# 5V_SYS_SUPPLY.net
KiCad netlist of a schematic drawn in Altium Designer
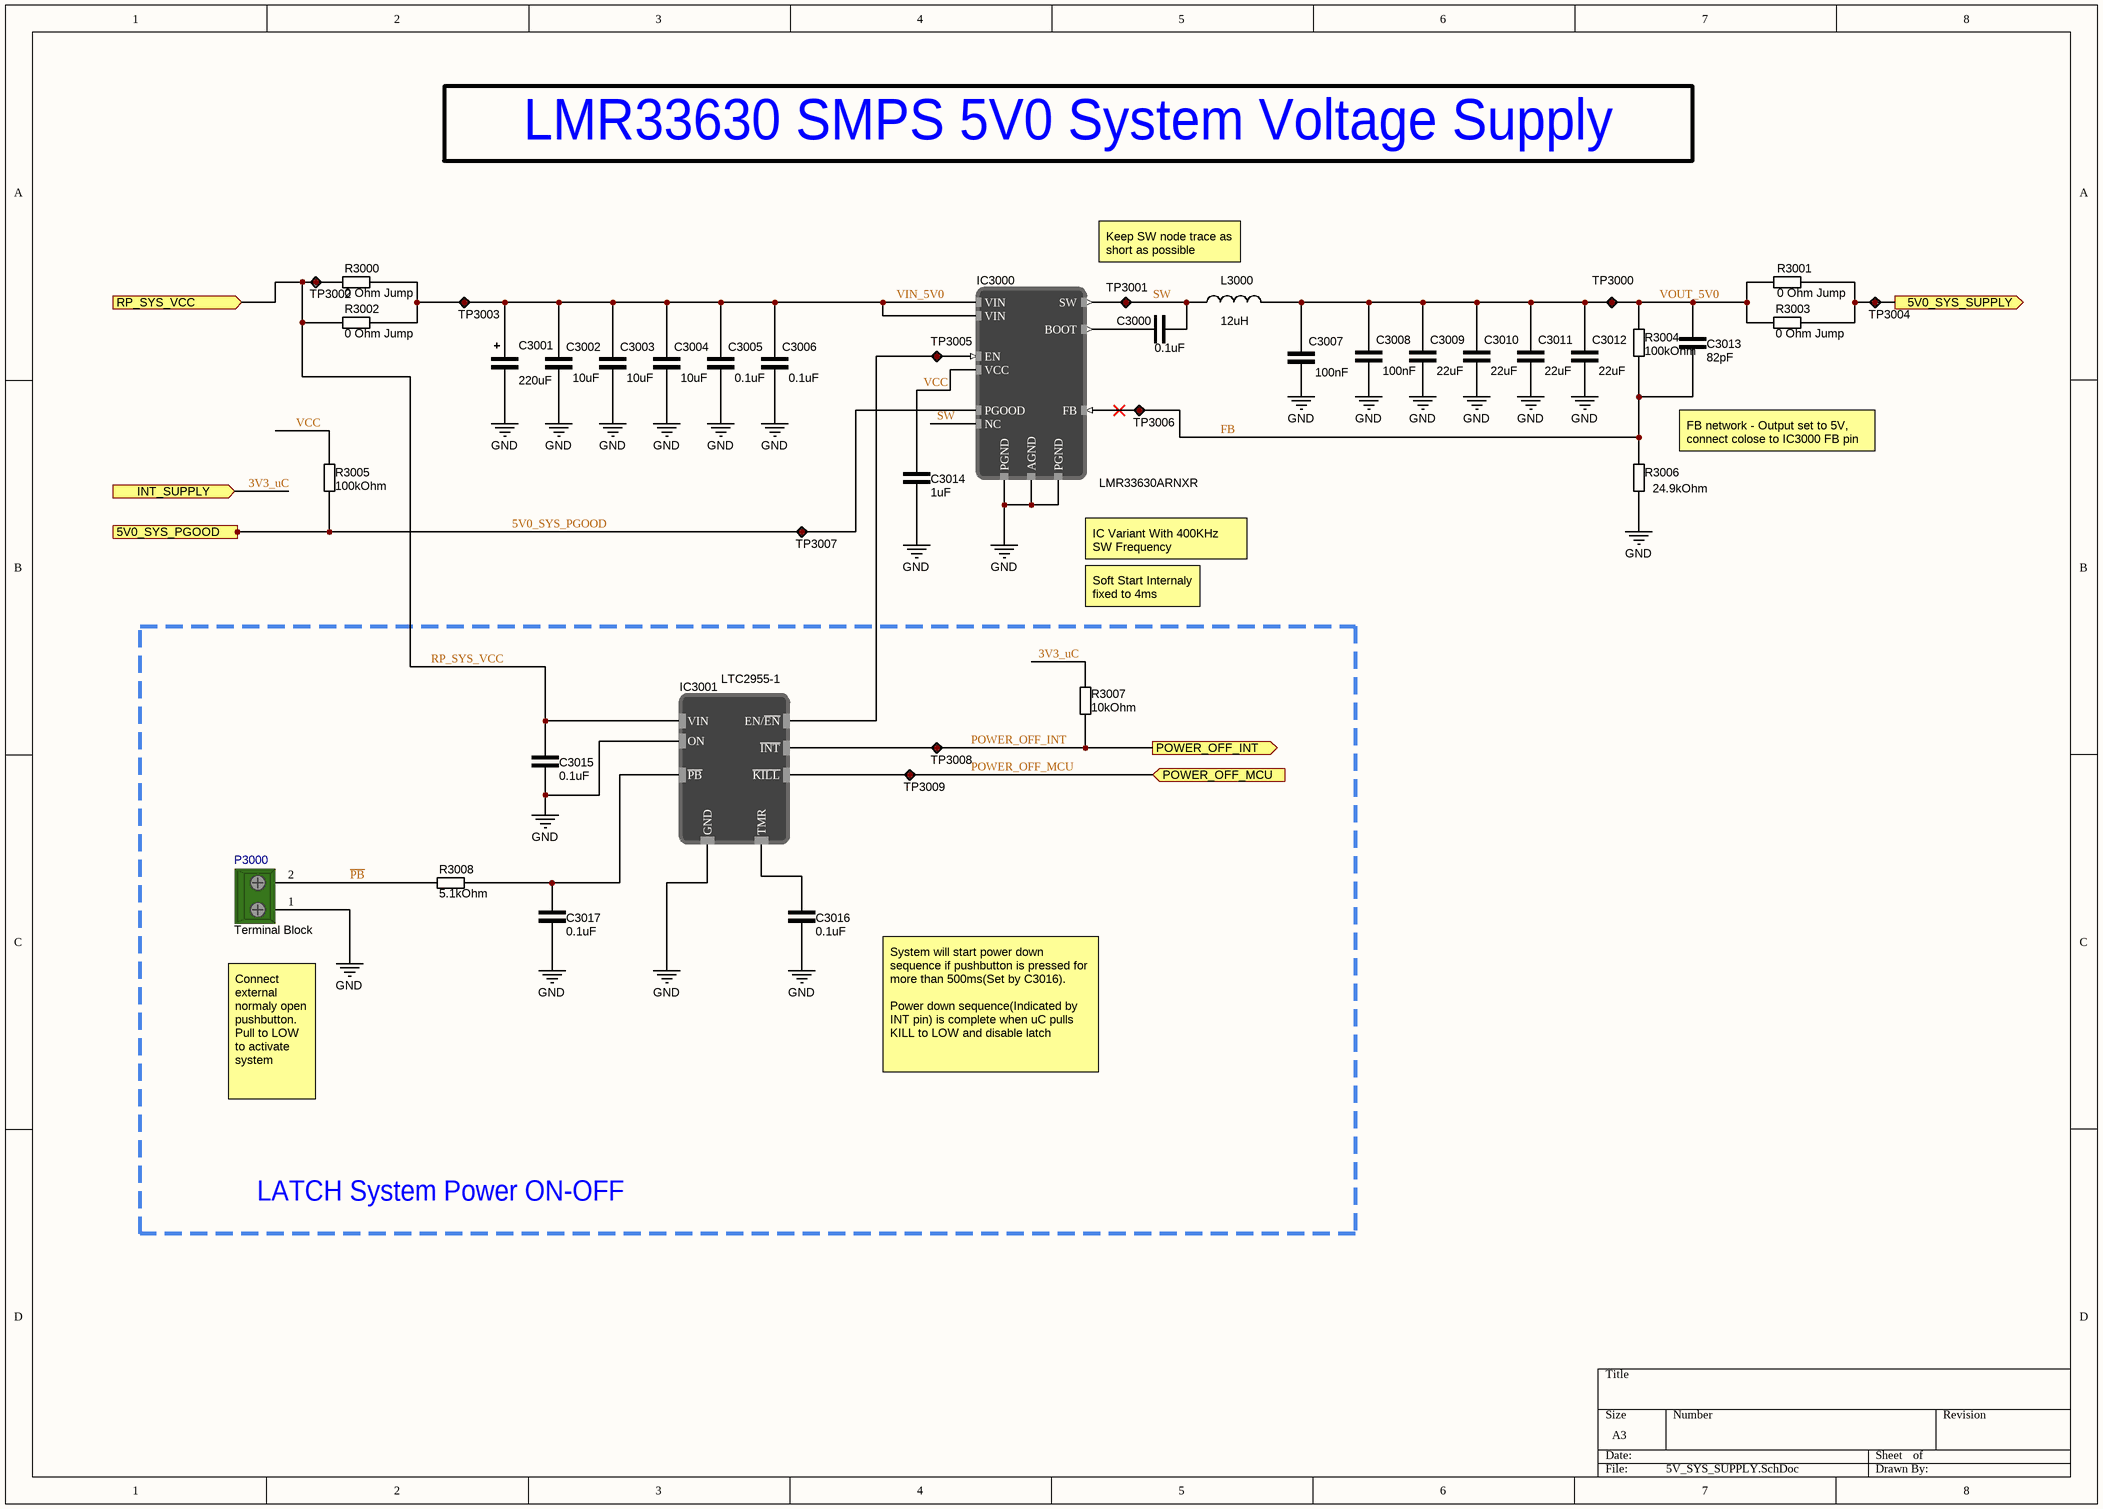
[diagram p0: 5V_SYS_SUPPLY.SchDoc]

(export (version "E")
  (design (tool "Eeschema 10.0.6"))
  (components
    (comp (ref "C3000")
      (value "0.1uF")
      (footprint "CAP_0603")
      (description "0.1 µF ±10% 50V Ceramic Capacitor X7R 0603 (1608 Metric)")
      (fields (field (name "DIGIKEY PART NUMBER") "1276-1000-1-ND"))
      (libsource (lib "") (part "C000018_1"))
    )
    (comp (ref "C3001")
      (value "220uF")
      (footprint "CAPAE109103X103M")
      (description "220 µF 50 V Aluminum Electrolytic Capacitors Radial, Can - SMD 7000 Hrs @ 105°C")
      (fields (field (name "DIGIKEY PART NUMBER") "493-9426-1-ND"))
      (libsource (lib "CapacitorsIntegrated") (part "C000019"))
    )
    (comp (ref "C3002")
      (value "10uF")
      (footprint "CAP_1206")
      (description "10 µF ±10% 50V Ceramic Capacitor X7R 1206 (3216 Metric)")
      (fields (field (name "DIGIKEY PART NUMBER") "1276-6767-1-ND"))
      (libsource (lib "CapacitorsIntegrated") (part "C000017"))
    )
    (comp (ref "C3003")
      (value "10uF")
      (footprint "CAP_1206")
      (description "10 µF ±10% 50V Ceramic Capacitor X7R 1206 (3216 Metric)")
      (fields (field (name "DIGIKEY PART NUMBER") "1276-6767-1-ND"))
      (libsource (lib "CapacitorsIntegrated") (part "C000017"))
    )
    (comp (ref "C3004")
      (value "10uF")
      (footprint "CAP_1206")
      (description "10 µF ±10% 50V Ceramic Capacitor X7R 1206 (3216 Metric)")
      (fields (field (name "DIGIKEY PART NUMBER") "1276-6767-1-ND"))
      (libsource (lib "CapacitorsIntegrated") (part "C000017"))
    )
    (comp (ref "C3005")
      (value "0.1uF")
      (footprint "CAP_0603")
      (description "0.1 µF ±10% 50V Ceramic Capacitor X7R 0603 (1608 Metric)")
      (fields (field (name "DIGIKEY PART NUMBER") "1276-1000-1-ND"))
      (libsource (lib "CapacitorsIntegrated") (part "C000018"))
    )
    (comp (ref "C3006")
      (value "0.1uF")
      (footprint "CAP_0603")
      (description "0.1 µF ±10% 50V Ceramic Capacitor X7R 0603 (1608 Metric)")
      (fields (field (name "DIGIKEY PART NUMBER") "1276-1000-1-ND"))
      (libsource (lib "CapacitorsIntegrated") (part "C000018"))
    )
    (comp (ref "C3007")
      (value "100nF")
      (footprint "CAP_0603")
      (description "0.1 µF ±10% 25V Ceramic Capacitor X7R 0603 (1608 Metric)")
      (fields (field (name "DIGIKEY PART NUMBER") "478-KAM15AR71E104KTCT-ND"))
      (libsource (lib "CapacitorsIntegrated") (part "C000007"))
    )
    (comp (ref "C3008")
      (value "100nF")
      (footprint "CAP_0603")
      (description "0.1 µF ±10% 25V Ceramic Capacitor X7R 0603 (1608 Metric)")
      (fields (field (name "DIGIKEY PART NUMBER") "478-KAM15AR71E104KTCT-ND"))
      (libsource (lib "CapacitorsIntegrated") (part "C000007"))
    )
    (comp (ref "C3009")
      (value "22uF")
      (footprint "CAP_1206")
      (description "22 µF ±10% 25V Ceramic Capacitor X5R 1206 (3216 Metric)")
      (fields (field (name "DIGIKEY PART NUMBER") "1276-3047-1-ND"))
      (libsource (lib "CapacitorsIntegrated") (part "C000020"))
    )
    (comp (ref "C3010")
      (value "22uF")
      (footprint "CAP_1206")
      (description "22 µF ±10% 25V Ceramic Capacitor X5R 1206 (3216 Metric)")
      (fields (field (name "DIGIKEY PART NUMBER") "1276-3047-1-ND"))
      (libsource (lib "CapacitorsIntegrated") (part "C000020"))
    )
    (comp (ref "C3011")
      (value "22uF")
      (footprint "CAP_1206")
      (description "22 µF ±10% 25V Ceramic Capacitor X5R 1206 (3216 Metric)")
      (fields (field (name "DIGIKEY PART NUMBER") "1276-3047-1-ND"))
      (libsource (lib "CapacitorsIntegrated") (part "C000020"))
    )
    (comp (ref "C3012")
      (value "22uF")
      (footprint "CAP_1206")
      (description "22 µF ±10% 25V Ceramic Capacitor X5R 1206 (3216 Metric)")
      (fields (field (name "DIGIKEY PART NUMBER") "1276-3047-1-ND"))
      (libsource (lib "CapacitorsIntegrated") (part "C000020"))
    )
    (comp (ref "C3013")
      (value "82pF")
      (footprint "CAP_0603")
      (description "82 pF ±1% 25V Ceramic Capacitor C0G, NP0 0603 (1608 Metric)")
      (fields (field (name "DIGIKEY PART NUMBER") "478-KGM15ACG1E820FTCT-ND"))
      (libsource (lib "CapacitorsIntegrated") (part "C000021"))
    )
    (comp (ref "C3014")
      (value "1uF")
      (footprint "CAP_0603")
      (description "1 µF ±10% 10V Ceramic Capacitor X7R 0603 (1608 Metric)")
      (fields (field (name "DIGIKEY PART NUMBER") "1276-1946-2-ND"))
      (libsource (lib "CapacitorsIntegrated") (part "C000011"))
    )
    (comp (ref "C3015")
      (value "0.1uF")
      (footprint "CAP_0603")
      (description "0.1 µF ±10% 50V Ceramic Capacitor X7R 0603 (1608 Metric)")
      (fields (field (name "DIGIKEY PART NUMBER") "1276-1000-1-ND"))
      (libsource (lib "CapacitorsIntegrated") (part "C000018"))
    )
    (comp (ref "C3016")
      (value "0.1uF")
      (footprint "CAP_0603")
      (description "0.1 µF ±10% 50V Ceramic Capacitor X7R 0603 (1608 Metric)")
      (fields (field (name "DIGIKEY PART NUMBER") "1276-1000-1-ND"))
      (libsource (lib "CapacitorsIntegrated") (part "C000018"))
    )
    (comp (ref "C3017")
      (value "0.1uF")
      (footprint "CAP_0603")
      (description "0.1 µF ±10% 50V Ceramic Capacitor X7R 0603 (1608 Metric)")
      (fields (field (name "DIGIKEY PART NUMBER") "1276-1000-1-ND"))
      (libsource (lib "CapacitorsIntegrated") (part "C000018"))
    )
    (comp (ref "IC3000")
      (value "LMR33630ARNXR")
      (footprint "VQFN-HR")
      (description "Buck Switching Regulator IC Positive Adjustable 1V 1 Output 3A 12-VFQFN")
      (fields
        (field (name "DIGIKEY PART NUMBER") "296-49764-1-ND")
        (field (name "MOUSER PART NUMBER") "595-LMR33630ARNXR")
      )
      (libsource (lib "IntegratedCircuits") (part "LMR33630ARNXR"))
    )
    (comp (ref "IC3001")
      (value "LTC2955-1")
      (footprint "TSOP65P280X100-8N")
      (description "Power Supply Controller Push Button, On/Off Controller TSOT-23-8")
      (fields
        (field (name "DIGIKEY PART NUMBER") "505-LTC2955CTS8-1#TRMPBFCT-ND")
        (field (name "MOUSER PART NUMBER") "584-C2955CTS8-1TMPF")
      )
      (libsource (lib "IntegratedCircuits") (part "LTC2955-1"))
    )
    (comp (ref "L3000")
      (value "12uH")
      (footprint "INDM120120X80N")
      (description "FIXED IND 12UH 5.9A 24 MOHM SMD")
      (fields (field (name "DIGIKEY PART NUMBER") "732-1224-1-ND"))
      (libsource (lib "InductorIntegrated") (part "L000007"))
    )
    (comp (ref "P3000")
      (value "Terminal Block")
      (footprint "TERM_BLOCK 5mm 2PIN")
      (description "Terminal block 90 deg 5mm 2PIN")
      (fields (field (name "DIGIKEY PART NUMBER") "2057-EB20-02-C-ND"))
      (libsource (lib "ElectroMechanical") (part "00000001"))
    )
    (comp (ref "R3000")
      (value "0 Ohm Jump")
      (footprint "RES_0805")
      (description "0 Ohms Jumper Chip Resistor 0805 (2012 Metric) Automotive AEC-Q200 Thick Film")
      (fields (field (name "DIGIKEY PART NUMBER") "P0.0ACT-ND"))
      (libsource (lib "ResistorsIntegrated") (part "R000011"))
    )
    (comp (ref "R3001")
      (value "0 Ohm Jump")
      (footprint "RES_1206")
      (description "0 Ohms Jumper Chip Resistor 1206 (3216 Metric) Automotive AEC-Q200 Thick Film")
      (fields (field (name "DIGIKEY PART NUMBER") "RMCF1206ZT0R00CT-ND"))
      (libsource (lib "") (part "R000012_1"))
    )
    (comp (ref "R3002")
      (value "0 Ohm Jump")
      (footprint "RES_0805")
      (description "0 Ohms Jumper Chip Resistor 0805 (2012 Metric) Automotive AEC-Q200 Thick Film")
      (fields (field (name "DIGIKEY PART NUMBER") "P0.0ACT-ND"))
      (libsource (lib "ResistorsIntegrated") (part "R000011"))
    )
    (comp (ref "R3003")
      (value "0 Ohm Jump")
      (footprint "RES_1206")
      (description "0 Ohms Jumper Chip Resistor 1206 (3216 Metric) Automotive AEC-Q200 Thick Film")
      (fields (field (name "DIGIKEY PART NUMBER") "RMCF1206ZT0R00CT-ND"))
      (libsource (lib "ResistorsIntegrated") (part "R000012"))
    )
    (comp (ref "R3004")
      (value "100kOhm")
      (footprint "RES_0603")
      (description "100 kOhms ±1% 0.1W, 1/10W Chip Resistor 0603 (1608 Metric) Automotive AEC-Q200 Thick Film")
      (fields (field (name "DIGIKEY PART NUMBER") "RMCF0603FG100KCT-ND"))
      (libsource (lib "ResistorsIntegrated") (part "R000006"))
    )
    (comp (ref "R3005")
      (value "100kOhm")
      (footprint "RES_0603")
      (description "100 kOhms ±1% 0.1W, 1/10W Chip Resistor 0603 (1608 Metric) Automotive AEC-Q200 Thick Film")
      (fields (field (name "DIGIKEY PART NUMBER") "RMCF0603FG100KCT-ND"))
      (libsource (lib "ResistorsIntegrated") (part "R000006"))
    )
    (comp (ref "R3006")
      (value "24.9kOhm")
      (footprint "RES_0603")
      (description "24.9 kOhms ±1% 0.1W, 1/10W Chip Resistor 0603 (1608 Metric) Automotive AEC-Q200 Thick Film")
      (fields (field (name "DIGIKEY PART NUMBER") "P24.9KHCT-ND"))
      (libsource (lib "ResistorsIntegrated") (part "R000017"))
    )
    (comp (ref "R3007")
      (value "10kOhm")
      (footprint "RES_0603")
      (description "10 kOhms ±1% 0.125W, 1/8W Chip Resistor 0603 (1608 Metric) Anti-Sulfur Thin Film")
      (fields (field (name "DIGIKEY PART NUMBER") "MCT0603-10.0K-CFCT-ND"))
      (libsource (lib "ResistorsIntegrated") (part "R000001"))
    )
    (comp (ref "R3008")
      (value "5.1kOhm")
      (footprint "RES_0603")
      (description "5.1 kOhms ±1% 0.1W, 1/10W Chip Resistor 0603 (1608 Metric) Moisture Resistant Thick Film")
      (fields (field (name "DIGIKEY PART NUMBER") "311-5.10KHRCT-ND"))
      (libsource (lib "ResistorsIntegrated") (part "R000013"))
    )
    (comp (ref "TP3000")
      (value "Test point")
      (footprint "TestPoint")
      (description "Test point 1mm")
      (libsource (lib "IntegratedCircuits") (part "TP002"))
    )
    (comp (ref "TP3001")
      (value "Test point")
      (footprint "TestPoint")
      (description "Test point 1mm")
      (libsource (lib "IntegratedCircuits") (part "TP002"))
    )
    (comp (ref "TP3002")
      (value "Test point")
      (footprint "TestPoint")
      (description "Test point 1mm")
      (libsource (lib "IntegratedCircuits") (part "TP002"))
    )
    (comp (ref "TP3003")
      (value "Test point")
      (footprint "TestPoint")
      (description "Test point 1mm")
      (libsource (lib "IntegratedCircuits") (part "TP002"))
    )
    (comp (ref "TP3004")
      (value "Test point")
      (footprint "TestPoint")
      (description "Test point 1mm")
      (libsource (lib "IntegratedCircuits") (part "TP002"))
    )
    (comp (ref "TP3005")
      (value "Test point")
      (footprint "TestPoint")
      (description "Test point 1mm")
      (libsource (lib "IntegratedCircuits") (part "TP002"))
    )
    (comp (ref "TP3006")
      (value "Test point")
      (footprint "TestPoint")
      (description "Test point 1mm")
      (libsource (lib "IntegratedCircuits") (part "TP002"))
    )
    (comp (ref "TP3007")
      (value "Test point")
      (footprint "TestPoint")
      (description "Test point 1mm")
      (libsource (lib "IntegratedCircuits") (part "TP002"))
    )
    (comp (ref "TP3008")
      (value "Test point")
      (footprint "TestPoint")
      (description "Test point 1mm")
      (libsource (lib "IntegratedCircuits") (part "TP002"))
    )
    (comp (ref "TP3009")
      (value "Test point")
      (footprint "TestPoint")
      (description "Test point 1mm")
      (libsource (lib "IntegratedCircuits") (part "TP002"))
    )
  )
  (nets
    (net (code "1") (name "/3V3_uC") (class "Default")
      (node (ref "R3007") (pin "2") (pinfunction "2_2") (pintype "passive"))
    )
    (net (code "2") (name "/5V0_SYS_PGOOD") (class "Default")
      (node (ref "IC3000") (pin "8") (pinfunction "PGOOD_8") (pintype "open_collector"))
      (node (ref "R3005") (pin "1") (pinfunction "1_1") (pintype "passive"))
      (node (ref "TP3007") (pin "1") (pinfunction "1_1") (pintype "passive"))
    )
    (net (code "3") (name "/5V0_SYS_SUPPLY") (class "Default")
      (node (ref "R3001") (pin "1") (pinfunction "1_1") (pintype "passive"))
      (node (ref "R3003") (pin "2") (pinfunction "2_2") (pintype "passive"))
      (node (ref "TP3004") (pin "1") (pinfunction "1_1") (pintype "passive"))
    )
    (net (code "4") (name "/FB") (class "Default")
      (node (ref "C3013") (pin "1") (pinfunction "1_1") (pintype "passive"))
      (node (ref "IC3000") (pin "7") (pinfunction "FB_7") (pintype "input"))
      (node (ref "R3004") (pin "1") (pinfunction "1_1") (pintype "passive"))
      (node (ref "R3006") (pin "2") (pinfunction "2_2") (pintype "passive"))
      (node (ref "TP3006") (pin "1") (pinfunction "1_1") (pintype "passive"))
    )
    (net (code "5") (name "/POWER_OFF_INT") (class "Default")
      (node (ref "IC3001") (pin "8") (pinfunction "~{INT}_8") (pintype "passive"))
      (node (ref "R3007") (pin "1") (pinfunction "1_1") (pintype "passive"))
      (node (ref "TP3008") (pin "1") (pinfunction "1_1") (pintype "passive"))
    )
    (net (code "6") (name "/POWER_OFF_MCU") (class "Default")
      (node (ref "IC3001") (pin "2") (pinfunction "~{KILL}_2") (pintype "passive"))
      (node (ref "TP3009") (pin "1") (pinfunction "1_1") (pintype "passive"))
    )
    (net (code "7") (name "/RP_SYS_VCC") (class "Default")
      (node (ref "C3015") (pin "2") (pinfunction "2_2") (pintype "passive"))
      (node (ref "IC3001") (pin "6") (pinfunction "VIN_6") (pintype "passive"))
      (node (ref "R3000") (pin "1") (pinfunction "1_1") (pintype "passive"))
      (node (ref "R3002") (pin "1") (pinfunction "1_1") (pintype "passive"))
      (node (ref "TP3002") (pin "1") (pinfunction "1_1") (pintype "passive"))
    )
    (net (code "8") (name "/SW") (class "Default")
      (node (ref "C3000") (pin "2") (pinfunction "2_2") (pintype "passive"))
      (node (ref "IC3000") (pin "12") (pinfunction "SW_12") (pintype "output"))
      (node (ref "IC3000") (pin "3") (pinfunction "NC_3") (pintype "tri_state"))
      (node (ref "L3000") (pin "1") (pinfunction "1_1") (pintype "passive"))
      (node (ref "TP3001") (pin "1") (pinfunction "1_1") (pintype "passive"))
    )
    (net (code "9") (name "/VCC") (class "Default")
      (node (ref "C3014") (pin "2") (pinfunction "2_2") (pintype "passive"))
      (node (ref "IC3000") (pin "5") (pinfunction "VCC_5") (pintype "power_in"))
      (node (ref "R3005") (pin "2") (pinfunction "2_2") (pintype "passive"))
    )
    (net (code "10") (name "/VIN_5V0") (class "Default")
      (node (ref "C3001") (pin "2") (pinfunction "2_2") (pintype "passive"))
      (node (ref "C3002") (pin "2") (pinfunction "2_2") (pintype "passive"))
      (node (ref "C3003") (pin "2") (pinfunction "2_2") (pintype "passive"))
      (node (ref "C3004") (pin "2") (pinfunction "2_2") (pintype "passive"))
      (node (ref "C3005") (pin "2") (pinfunction "2_2") (pintype "passive"))
      (node (ref "C3006") (pin "2") (pinfunction "2_2") (pintype "passive"))
      (node (ref "IC3000") (pin "10") (pinfunction "VIN_10") (pintype "power_in"))
      (node (ref "IC3000") (pin "2") (pinfunction "VIN_2") (pintype "power_in"))
      (node (ref "R3000") (pin "2") (pinfunction "2_2") (pintype "passive"))
      (node (ref "R3002") (pin "2") (pinfunction "2_2") (pintype "passive"))
      (node (ref "TP3003") (pin "1") (pinfunction "1_1") (pintype "passive"))
    )
    (net (code "11") (name "/VOUT_5V0") (class "Default")
      (node (ref "C3007") (pin "2") (pinfunction "2_2") (pintype "passive"))
      (node (ref "C3008") (pin "2") (pinfunction "2_2") (pintype "passive"))
      (node (ref "C3009") (pin "2") (pinfunction "2_2") (pintype "passive"))
      (node (ref "C3010") (pin "2") (pinfunction "2_2") (pintype "passive"))
      (node (ref "C3011") (pin "2") (pinfunction "2_2") (pintype "passive"))
      (node (ref "C3012") (pin "2") (pinfunction "2_2") (pintype "passive"))
      (node (ref "C3013") (pin "2") (pinfunction "2_2") (pintype "passive"))
      (node (ref "L3000") (pin "2") (pinfunction "2_2") (pintype "passive"))
      (node (ref "R3001") (pin "2") (pinfunction "2_2") (pintype "passive"))
      (node (ref "R3003") (pin "1") (pinfunction "1_1") (pintype "passive"))
      (node (ref "R3004") (pin "2") (pinfunction "2_2") (pintype "passive"))
      (node (ref "TP3000") (pin "1") (pinfunction "1_1") (pintype "passive"))
    )
    (net (code "12") (name "/~{PB}") (class "Default")
      (node (ref "P3000") (pin "2") (pinfunction "pin2_2") (pintype "passive"))
      (node (ref "R3008") (pin "1") (pinfunction "1_1") (pintype "passive"))
    )
    (net (code "13") (name "GND") (class "Default")
      (node (ref "C3001") (pin "1") (pinfunction "1_1") (pintype "passive"))
      (node (ref "C3002") (pin "1") (pinfunction "1_1") (pintype "passive"))
      (node (ref "C3003") (pin "1") (pinfunction "1_1") (pintype "passive"))
      (node (ref "C3004") (pin "1") (pinfunction "1_1") (pintype "passive"))
      (node (ref "C3005") (pin "1") (pinfunction "1_1") (pintype "passive"))
      (node (ref "C3006") (pin "1") (pinfunction "1_1") (pintype "passive"))
      (node (ref "C3008") (pin "1") (pinfunction "1_1") (pintype "passive"))
      (node (ref "C3009") (pin "1") (pinfunction "1_1") (pintype "passive"))
      (node (ref "C3010") (pin "1") (pinfunction "1_1") (pintype "passive"))
      (node (ref "C3011") (pin "1") (pinfunction "1_1") (pintype "passive"))
      (node (ref "C3012") (pin "1") (pinfunction "1_1") (pintype "passive"))
      (node (ref "C3014") (pin "1") (pinfunction "1_1") (pintype "passive"))
      (node (ref "C3015") (pin "1") (pinfunction "1_1") (pintype "passive"))
      (node (ref "C3016") (pin "1") (pinfunction "1_1") (pintype "passive"))
      (node (ref "C3017") (pin "1") (pinfunction "1_1") (pintype "passive"))
      (node (ref "IC3000") (pin "1") (pinfunction "PGND_1") (pintype "power_in"))
      (node (ref "IC3000") (pin "11") (pinfunction "PGND_11") (pintype "power_in"))
      (node (ref "IC3000") (pin "6") (pinfunction "AGND_6") (pintype "power_in"))
      (node (ref "IC3001") (pin "1") (pinfunction "ON_1") (pintype "passive"))
      (node (ref "IC3001") (pin "4") (pinfunction "GND_4") (pintype "power_in"))
      (node (ref "P3000") (pin "1") (pinfunction "pin1_1") (pintype "passive"))
      (node (ref "R3006") (pin "1") (pinfunction "1_1") (pintype "passive"))
    )
    (net (code "14") (name "Net-(IC3000-BOOT)") (class "Default")
      (node (ref "C3000") (pin "1") (pinfunction "1_1") (pintype "passive"))
      (node (ref "IC3000") (pin "4") (pinfunction "BOOT_4") (pintype "output"))
    )
    (net (code "15") (name "Net-(IC3000-EN)") (class "Default")
      (node (ref "IC3000") (pin "9") (pinfunction "EN_9") (pintype "input"))
      (node (ref "IC3001") (pin "7") (pinfunction "EN/~{EN}_7") (pintype "open_collector"))
      (node (ref "TP3005") (pin "1") (pinfunction "1_1") (pintype "passive"))
    )
    (net (code "16") (name "Net-(IC3001-TMR)") (class "Default")
      (node (ref "C3016") (pin "2") (pinfunction "2_2") (pintype "passive"))
      (node (ref "IC3001") (pin "3") (pinfunction "TMR_3") (pintype "passive"))
    )
    (net (code "17") (name "Net-(IC3001-~{PB})") (class "Default")
      (node (ref "C3017") (pin "2") (pinfunction "2_2") (pintype "passive"))
      (node (ref "IC3001") (pin "5") (pinfunction "~{PB}_5") (pintype "passive"))
      (node (ref "R3008") (pin "2") (pinfunction "2_2") (pintype "passive"))
    )
    (net (code "18") (name "unconnected-(C3007-Pad1)") (class "Default")
      (node (ref "C3007") (pin "1") (pinfunction "1_1") (pintype "passive"))
    )
  )
)
